# PowerBoard.net
KiCad netlist of a schematic drawn in EAGLE
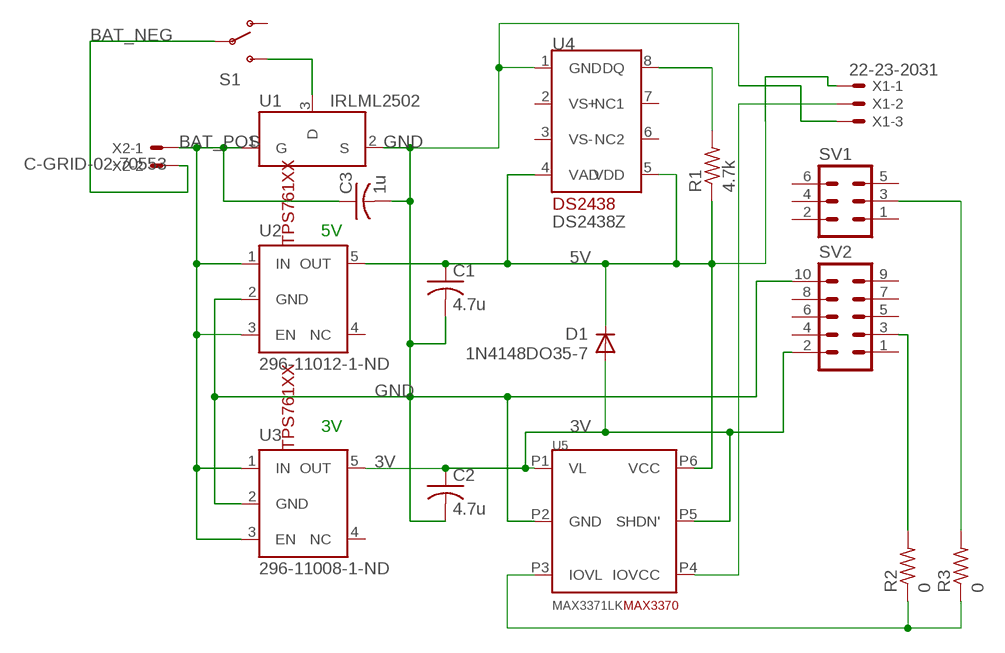
[diagram p0: schematic, sheet 1]

(export (version "E")
  (design (tool "Eeschema 10.0.6"))
  (components
    (comp (ref "C1")
      (value "4.7u")
      (footprint "eagle-import:C0805")
      (libsource (lib "eagle-import") (part "C-USC0805"))
    )
    (comp (ref "C2")
      (value "4.7u")
      (footprint "eagle-import:C0805")
      (libsource (lib "eagle-import") (part "C-USC0805"))
    )
    (comp (ref "C3")
      (value "1u")
      (footprint "eagle-import:C0805")
      (libsource (lib "eagle-import") (part "C-USC0805"))
    )
    (comp (ref "D1")
      (value "1N4148DO35-7")
      (footprint "eagle-import:DO35-7")
      (libsource (lib "eagle-import") (part "1N4148DO35-7"))
    )
    (comp (ref "R1")
      (value "4.7k")
      (footprint "eagle-import:M0805")
      (libsource (lib "eagle-import") (part "R-US_M0805"))
    )
    (comp (ref "R2")
      (value "0")
      (footprint "eagle-import:R0805")
      (libsource (lib "eagle-import") (part "R-US_R0805"))
    )
    (comp (ref "R3")
      (value "0")
      (footprint "eagle-import:R0805")
      (libsource (lib "eagle-import") (part "R-US_R0805"))
    )
    (comp (ref "S1")
      (value "SWITCH-SPST-SMD-A")
      (footprint "eagle-import:SWITCH-SPST-SMD-A")
      (libsource (lib "eagle-import") (part "SWITCH-SPST-SMD-A"))
    )
    (comp (ref "SV1")
      (value "MA03-2")
      (footprint "eagle-import:MA03-2")
      (libsource (lib "eagle-import") (part "MA03-2"))
    )
    (comp (ref "SV2")
      (value "MA05-2")
      (footprint "eagle-import:MA05-2")
      (libsource (lib "eagle-import") (part "MA05-2"))
    )
    (comp (ref "U1")
      (value "IRLML2502")
      (footprint "eagle-import:SOT23")
      (libsource (lib "eagle-import") (part "IRLML2502"))
    )
    (comp (ref "U2")
      (value "296-11012-1-ND")
      (footprint "eagle-import:SOT23-DBV")
      (libsource (lib "eagle-import") (part "296-11012-1-ND"))
    )
    (comp (ref "U3")
      (value "296-11008-1-ND")
      (footprint "eagle-import:SOT23-DBV")
      (libsource (lib "eagle-import") (part "296-11012-1-ND"))
    )
    (comp (ref "U4")
      (value "DS2438Z")
      (footprint "eagle-import:SOIC08")
      (libsource (lib "eagle-import") (part "DS2438Z"))
    )
    (comp (ref "U5")
      (value "MAX3371LK")
      (footprint "eagle-import:6-LEAD-SC70")
      (libsource (lib "eagle-import") (part "MAX3371LK"))
    )
    (comp (ref "X1")
      (value "22-23-2031")
      (footprint "eagle-import:22-23-2031")
      (fields (field (name "MF") "MOLEX"))
      (libsource (lib "eagle-import") (part "22-23-2031"))
    )
    (comp (ref "X2")
      (value "C-GRID-02-70553")
      (footprint "eagle-import:70553-02")
      (libsource (lib "eagle-import") (part "C-GRID-02-70553"))
    )
  )
  (nets
    (net (code "1") (name "/3V") (class "Default")
      (node (ref "C2") (pin "1") (pinfunction "1_1") (pintype "passive"))
      (node (ref "D1") (pin "A") (pinfunction "A_A") (pintype "passive"))
      (node (ref "SV2") (pin "2") (pinfunction "2_2") (pintype "passive"))
      (node (ref "U3") (pin "5") (pinfunction "OUT_5") (pintype "output"))
      (node (ref "U5") (pin "P1") (pinfunction "VL_P1") (pintype "bidirectional"))
      (node (ref "U5") (pin "P5") (pinfunction "SHDN'_P5") (pintype "bidirectional"))
    )
    (net (code "2") (name "/5V") (class "Default")
      (node (ref "C1") (pin "1") (pinfunction "1_1") (pintype "passive"))
      (node (ref "D1") (pin "C") (pinfunction "C_C") (pintype "passive"))
      (node (ref "R1") (pin "1") (pinfunction "1_1") (pintype "passive"))
      (node (ref "U2") (pin "5") (pinfunction "OUT_5") (pintype "output"))
      (node (ref "U4") (pin "4") (pinfunction "VAD_4") (pintype "bidirectional"))
      (node (ref "U4") (pin "5") (pinfunction "VDD_5") (pintype "power_in"))
      (node (ref "U5") (pin "P6") (pinfunction "VCC_P6") (pintype "power_in"))
      (node (ref "X1") (pin "1") (pinfunction "S_1") (pintype "passive"))
    )
    (net (code "3") (name "/BAT_NEG") (class "Default")
      (node (ref "S1") (pin "2") (pinfunction "P_2") (pintype "passive"))
      (node (ref "X2") (pin "2") (pinfunction "S_2") (pintype "passive"))
    )
    (net (code "4") (name "/BAT_POS") (class "Default")
      (node (ref "C3") (pin "1") (pinfunction "1_1") (pintype "passive"))
      (node (ref "U1") (pin "1") (pinfunction "G_1") (pintype "input"))
      (node (ref "U2") (pin "1") (pinfunction "IN_1") (pintype "input"))
      (node (ref "U2") (pin "3") (pinfunction "EN_3") (pintype "bidirectional"))
      (node (ref "U3") (pin "1") (pinfunction "IN_1") (pintype "input"))
      (node (ref "U3") (pin "3") (pinfunction "EN_3") (pintype "bidirectional"))
      (node (ref "X2") (pin "1") (pinfunction "S_1") (pintype "passive"))
    )
    (net (code "5") (name "/GND") (class "Default")
      (node (ref "C1") (pin "2") (pinfunction "2_2") (pintype "passive"))
      (node (ref "C2") (pin "2") (pinfunction "2_2") (pintype "passive"))
      (node (ref "C3") (pin "2") (pinfunction "2_2") (pintype "passive"))
      (node (ref "SV2") (pin "10") (pinfunction "10_10") (pintype "passive"))
      (node (ref "U1") (pin "2") (pinfunction "S_2") (pintype "input"))
      (node (ref "U2") (pin "2") (pinfunction "GND_2") (pintype "power_in"))
      (node (ref "U3") (pin "2") (pinfunction "GND_2") (pintype "power_in"))
      (node (ref "U4") (pin "1") (pinfunction "GND_1") (pintype "power_in"))
      (node (ref "U5") (pin "P2") (pinfunction "GND_P2") (pintype "power_in"))
      (node (ref "X1") (pin "3") (pinfunction "S_3") (pintype "passive"))
    )
    (net (code "6") (name "Net-(R2-Pad2)") (class "Default")
      (node (ref "R2") (pin "2") (pinfunction "2_2") (pintype "passive"))
      (node (ref "SV2") (pin "3") (pinfunction "3_3") (pintype "passive"))
    )
    (net (code "7") (name "Net-(R3-Pad2)") (class "Default")
      (node (ref "R3") (pin "2") (pinfunction "2_2") (pintype "passive"))
      (node (ref "SV1") (pin "3") (pinfunction "3_3") (pintype "passive"))
    )
    (net (code "8") (name "Net-(S1-S)") (class "Default")
      (node (ref "S1") (pin "3") (pinfunction "S_3") (pintype "passive"))
      (node (ref "U1") (pin "3") (pinfunction "D_3") (pintype "power_in"))
    )
    (net (code "9") (name "Net-(U4-DQ)") (class "Default")
      (node (ref "R1") (pin "2") (pinfunction "2_2") (pintype "passive"))
      (node (ref "U4") (pin "8") (pinfunction "DQ_8") (pintype "bidirectional"))
    )
    (net (code "10") (name "Net-(U5-IOVCC)") (class "Default")
      (node (ref "U5") (pin "P4") (pinfunction "IOVCC_P4") (pintype "power_in"))
      (node (ref "X1") (pin "2") (pinfunction "S_2") (pintype "passive"))
    )
    (net (code "11") (name "Net-(U5-IOVL)") (class "Default")
      (node (ref "R2") (pin "1") (pinfunction "1_1") (pintype "passive"))
      (node (ref "R3") (pin "1") (pinfunction "1_1") (pintype "passive"))
      (node (ref "U5") (pin "P3") (pinfunction "IOVL_P3") (pintype "bidirectional"))
    )
    (net (code "12") (name "unconnected-(S1-O-Pad1)") (class "Default")
      (node (ref "S1") (pin "1") (pinfunction "O_1") (pintype "passive"))
    )
    (net (code "13") (name "unconnected-(SV1-Pad1)") (class "Default")
      (node (ref "SV1") (pin "1") (pinfunction "1_1") (pintype "passive"))
    )
    (net (code "14") (name "unconnected-(SV1-Pad2)") (class "Default")
      (node (ref "SV1") (pin "2") (pinfunction "2_2") (pintype "passive"))
    )
    (net (code "15") (name "unconnected-(SV1-Pad4)") (class "Default")
      (node (ref "SV1") (pin "4") (pinfunction "4_4") (pintype "passive"))
    )
    (net (code "16") (name "unconnected-(SV1-Pad5)") (class "Default")
      (node (ref "SV1") (pin "5") (pinfunction "5_5") (pintype "passive"))
    )
    (net (code "17") (name "unconnected-(SV1-Pad6)") (class "Default")
      (node (ref "SV1") (pin "6") (pinfunction "6_6") (pintype "passive"))
    )
    (net (code "18") (name "unconnected-(SV2-Pad1)") (class "Default")
      (node (ref "SV2") (pin "1") (pinfunction "1_1") (pintype "passive"))
    )
    (net (code "19") (name "unconnected-(SV2-Pad4)") (class "Default")
      (node (ref "SV2") (pin "4") (pinfunction "4_4") (pintype "passive"))
    )
    (net (code "20") (name "unconnected-(SV2-Pad5)") (class "Default")
      (node (ref "SV2") (pin "5") (pinfunction "5_5") (pintype "passive"))
    )
    (net (code "21") (name "unconnected-(SV2-Pad6)") (class "Default")
      (node (ref "SV2") (pin "6") (pinfunction "6_6") (pintype "passive"))
    )
    (net (code "22") (name "unconnected-(SV2-Pad7)") (class "Default")
      (node (ref "SV2") (pin "7") (pinfunction "7_7") (pintype "passive"))
    )
    (net (code "23") (name "unconnected-(SV2-Pad8)") (class "Default")
      (node (ref "SV2") (pin "8") (pinfunction "8_8") (pintype "passive"))
    )
    (net (code "24") (name "unconnected-(SV2-Pad9)") (class "Default")
      (node (ref "SV2") (pin "9") (pinfunction "9_9") (pintype "passive"))
    )
    (net (code "25") (name "unconnected-(U2-NC-Pad4)") (class "Default")
      (node (ref "U2") (pin "4") (pinfunction "NC_4") (pintype "no_connect"))
    )
    (net (code "26") (name "unconnected-(U3-NC-Pad4)") (class "Default")
      (node (ref "U3") (pin "4") (pinfunction "NC_4") (pintype "no_connect"))
    )
    (net (code "27") (name "unconnected-(U4-NC1-Pad7)") (class "Default")
      (node (ref "U4") (pin "7") (pinfunction "NC1_7") (pintype "no_connect"))
    )
    (net (code "28") (name "unconnected-(U4-NC2-Pad6)") (class "Default")
      (node (ref "U4") (pin "6") (pinfunction "NC2_6") (pintype "no_connect"))
    )
    (net (code "29") (name "unconnected-(U4-VS+-Pad2)") (class "Default")
      (node (ref "U4") (pin "2") (pinfunction "VS+_2") (pintype "bidirectional"))
    )
    (net (code "30") (name "unconnected-(U4-VS--Pad3)") (class "Default")
      (node (ref "U4") (pin "3") (pinfunction "VS-_3") (pintype "bidirectional"))
    )
  )
)
